# 021_BUTTONs_LEDs.net
KiCad netlist of a schematic drawn in Altium Designer
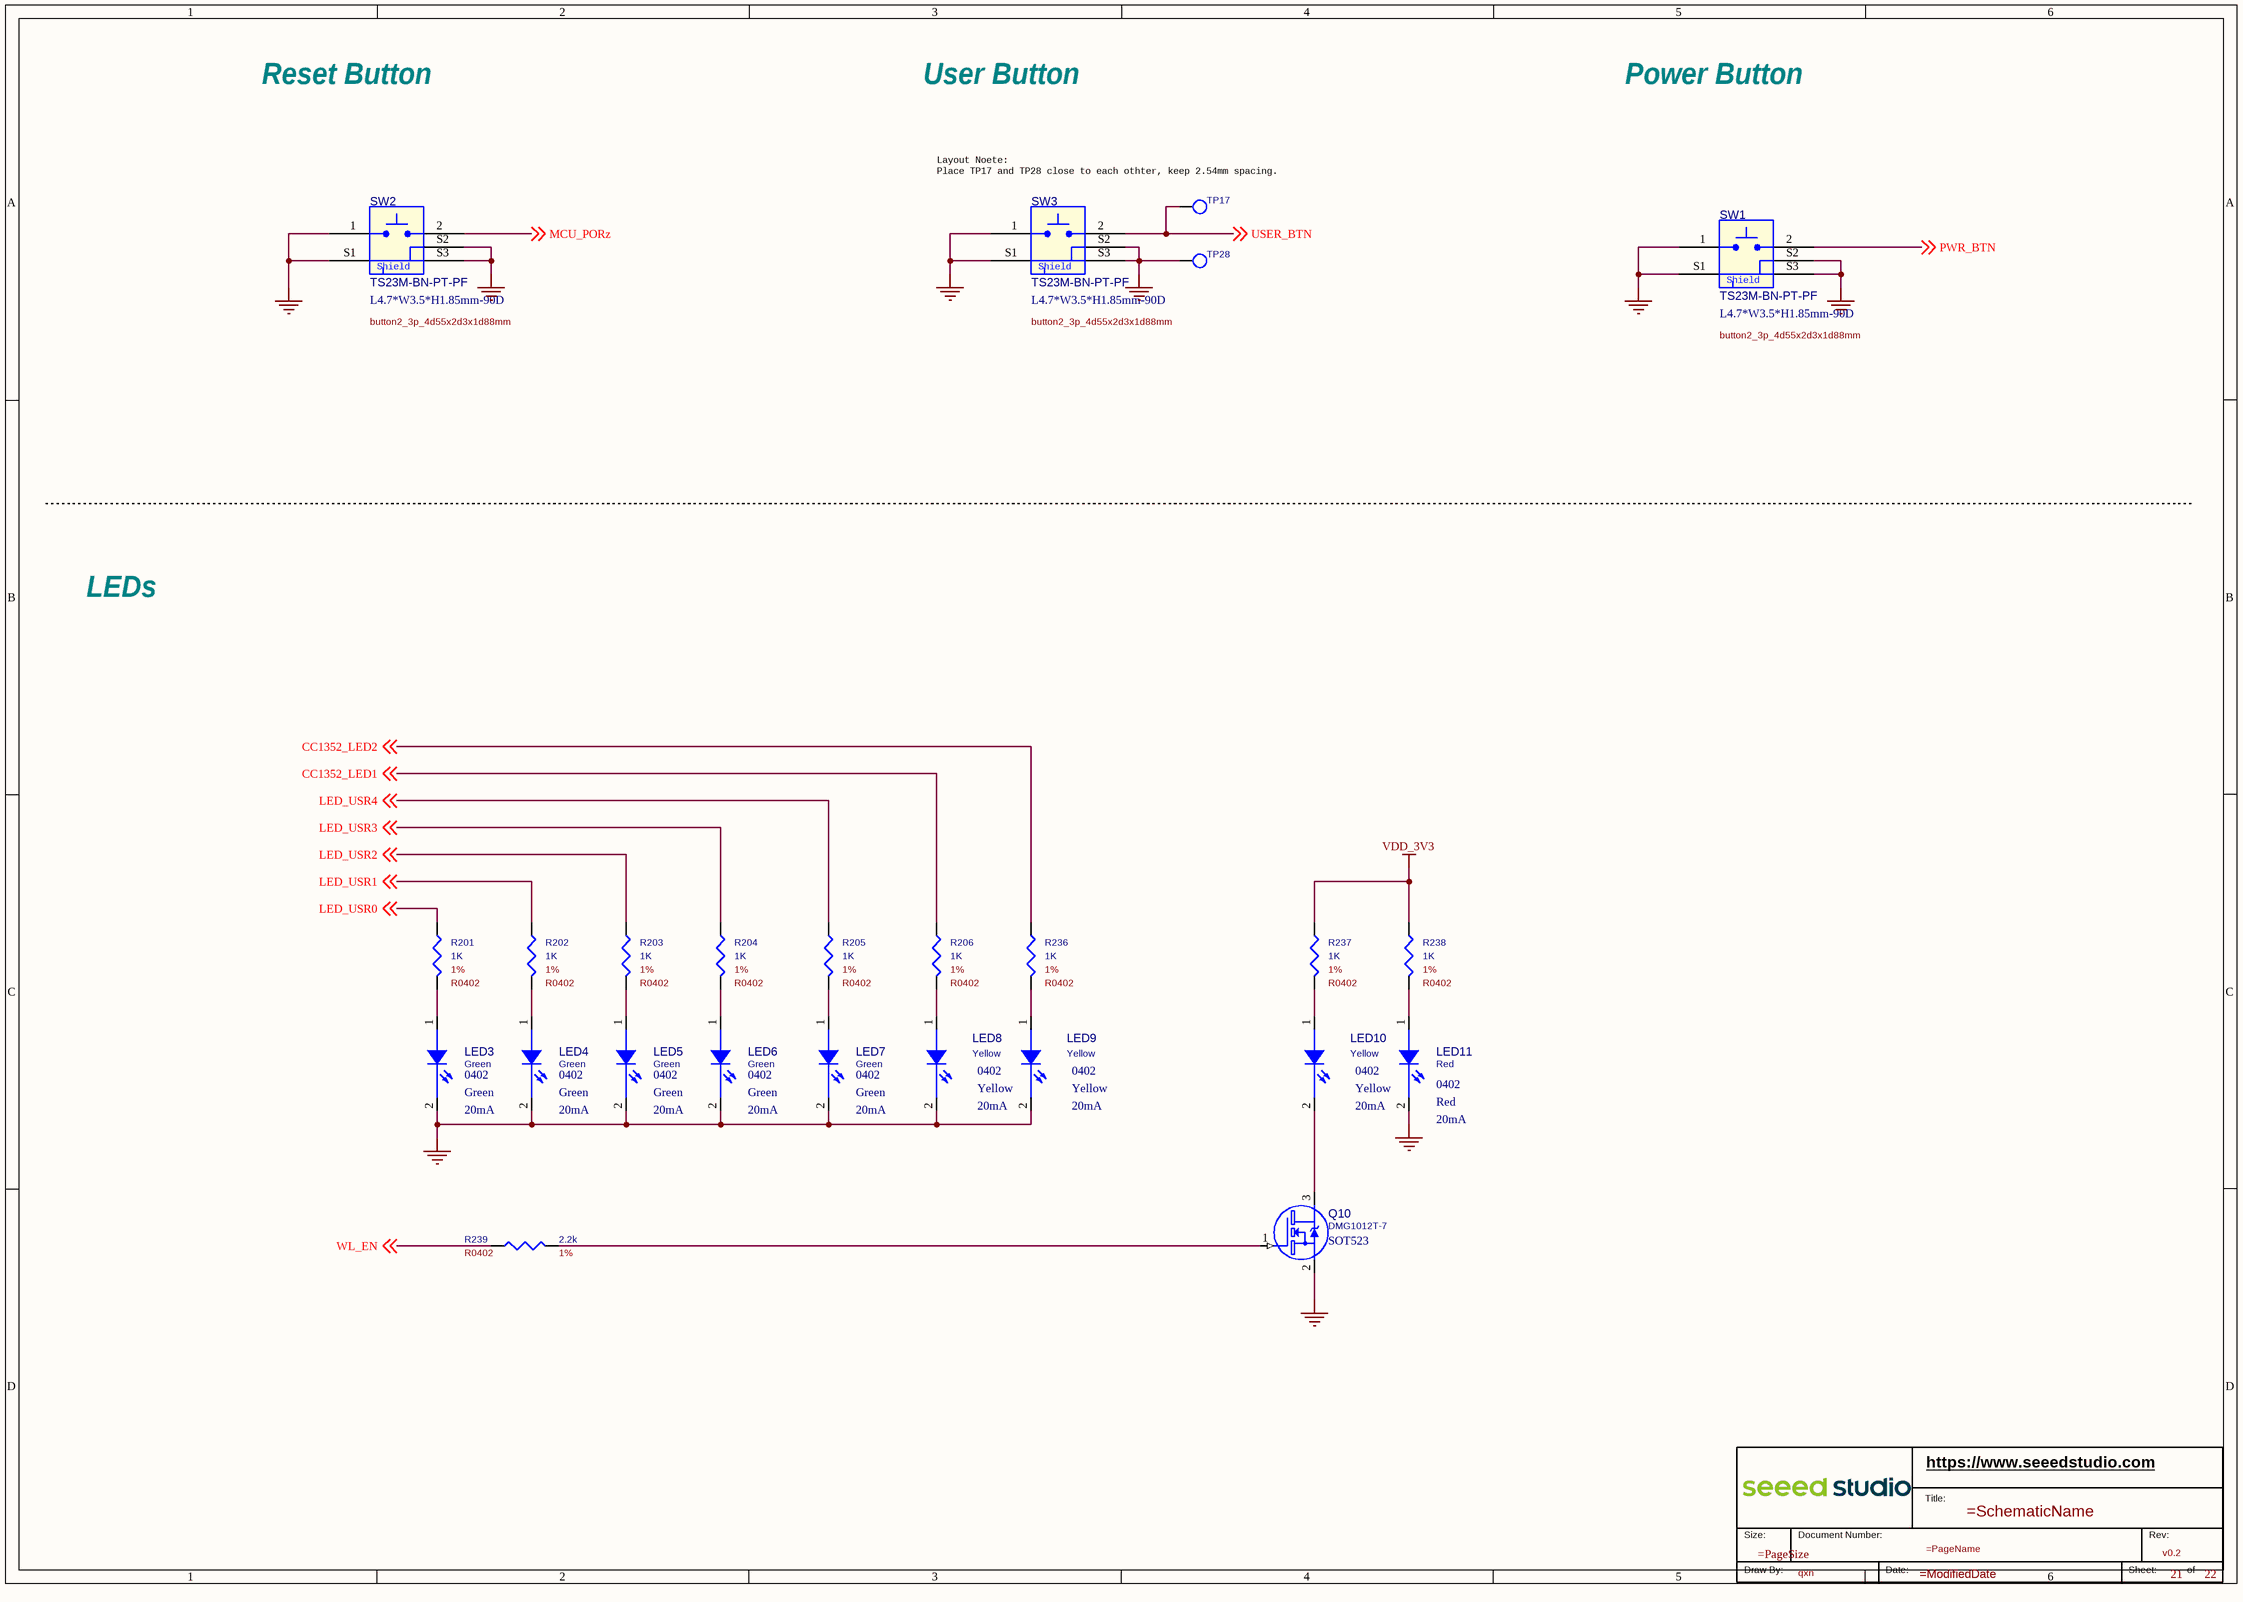
[diagram p0: 021_BUTTONs & LEDs.SchDoc]

(export (version "E")
  (design (tool "Eeschema 10.0.6"))
  (components
    (comp (ref "LED3")
      (value "Green")
      (footprint "led0402")
      (description "DIO, LED, Green, 20mA, --, --, 0402")
      (fields
        (field (name "MANUFACTURER") "Bright")
        (field (name "MANUFACTURER PART NUMBER") "19-217/BHC-ZL1M2RY/3T")
        (field (name "PACKAGE SIZE") "0402")
        (field (name "LED COLOR") "Green")
        (field (name "RATED CURRENT") "20mA")
      )
      (libsource (lib "*") (part "Single LED"))
    )
    (comp (ref "LED4")
      (value "Green")
      (footprint "led0402")
      (description "DIO, LED, Green, 20mA, --, --, 0402")
      (fields
        (field (name "MANUFACTURER") "Bright")
        (field (name "MANUFACTURER PART NUMBER") "19-217/BHC-ZL1M2RY/3T")
        (field (name "PACKAGE SIZE") "0402")
        (field (name "LED COLOR") "Green")
        (field (name "RATED CURRENT") "20mA")
      )
      (libsource (lib "*") (part "Single LED"))
    )
    (comp (ref "LED5")
      (value "Green")
      (footprint "led0402")
      (description "DIO, LED, Green, 20mA, --, --, 0402")
      (fields
        (field (name "MANUFACTURER") "Bright")
        (field (name "MANUFACTURER PART NUMBER") "19-217/BHC-ZL1M2RY/3T")
        (field (name "PACKAGE SIZE") "0402")
        (field (name "LED COLOR") "Green")
        (field (name "RATED CURRENT") "20mA")
      )
      (libsource (lib "*") (part "Single LED"))
    )
    (comp (ref "LED6")
      (value "Green")
      (footprint "led0402")
      (description "DIO, LED, Green, 20mA, --, --, 0402")
      (fields
        (field (name "MANUFACTURER") "Bright")
        (field (name "MANUFACTURER PART NUMBER") "19-217/BHC-ZL1M2RY/3T")
        (field (name "PACKAGE SIZE") "0402")
        (field (name "LED COLOR") "Green")
        (field (name "RATED CURRENT") "20mA")
      )
      (libsource (lib "*") (part "Single LED"))
    )
    (comp (ref "LED7")
      (value "Green")
      (footprint "led0402")
      (description "DIO, LED, Green, 20mA, --, --, 0402")
      (fields
        (field (name "MANUFACTURER") "Bright")
        (field (name "MANUFACTURER PART NUMBER") "19-217/BHC-ZL1M2RY/3T")
        (field (name "PACKAGE SIZE") "0402")
        (field (name "LED COLOR") "Green")
        (field (name "RATED CURRENT") "20mA")
      )
      (libsource (lib "*") (part "Single LED"))
    )
    (comp (ref "LED8")
      (value "Yellow")
      (footprint "led0402")
      (description "DIO, LED, Yellow, 20mA, --, --, 0402")
      (fields
        (field (name "PACKAGE SIZE") "0402")
        (field (name "LED COLOR") "Yellow")
        (field (name "RATED CURRENT") "20mA")
        (field (name "MANUFACTURER") "Everlight")
        (field (name "Comment") "Single LED")
      )
      (libsource (lib "*") (part "Single LED"))
    )
    (comp (ref "LED9")
      (value "Yellow")
      (footprint "led0402")
      (description "DIO, LED, Yellow, 20mA, --, --, 0402")
      (fields
        (field (name "PACKAGE SIZE") "0402")
        (field (name "LED COLOR") "Yellow")
        (field (name "RATED CURRENT") "20mA")
        (field (name "MANUFACTURER") "Everlight")
        (field (name "Comment") "Single LED")
      )
      (libsource (lib "*") (part "Single LED"))
    )
    (comp (ref "LED10")
      (value "Yellow")
      (footprint "led0402")
      (description "DIO, LED, Yellow, 20mA, --, --, 0402")
      (fields
        (field (name "PACKAGE SIZE") "0402")
        (field (name "LED COLOR") "Yellow")
        (field (name "RATED CURRENT") "20mA")
        (field (name "MANUFACTURER") "Everlight")
        (field (name "Comment") "Single LED")
      )
      (libsource (lib "*") (part "Single LED"))
    )
    (comp (ref "LED11")
      (value "Red")
      (footprint "led0402")
      (description "DIO, LED, Red, 20mA, , , 0402")
      (fields
        (field (name "MANUFACTURER") "Bright")
        (field (name "MANUFACTURER PART NUMBER") "19-217/BHC-ZL1M2RY/3T")
        (field (name "PACKAGE SIZE") "0402")
        (field (name "LED COLOR") "Red")
        (field (name "RATED CURRENT") "20mA")
      )
      (libsource (lib "*") (part "Single LED"))
    )
    (comp (ref "Q10")
      (value "DMG1012T-7")
      (footprint "SOT_523")
      (description "XSTR, MOSFET, N-Channel, DMG1012T-7, 20V, 630mA, SOT523, SMD")
      (fields
        (field (name "MANUFACTURER") "Diodes")
        (field (name "PACKAGE SIZE") "SOT523")
        (field (name "Comment") "NMOS_123")
      )
      (libsource (lib "*") (part "NMOS_123"))
    )
    (comp (ref "R201")
      (value "1K")
      (footprint "R0402")
      (description "RES, Thick Film, 1K, 1%, 1/16W, SMD, 0402")
      (fields
        (field (name "RATING") "1%")
        (field (name "PCB FOOTPRINT") "R0402")
        (field (name "MANUFACTURER PART NUMBER") "RC0402JR-071KL")
        (field (name "MANUFACTURER") "YAGEO")
      )
      (libsource (lib "*") (part "R"))
    )
    (comp (ref "R202")
      (value "1K")
      (footprint "R0402")
      (description "RES, Thick Film, 1K, 1%, 1/16W, SMD, 0402")
      (fields
        (field (name "RATING") "1%")
        (field (name "PCB FOOTPRINT") "R0402")
        (field (name "MANUFACTURER PART NUMBER") "RC0402JR-071KL")
        (field (name "MANUFACTURER") "YAGEO")
      )
      (libsource (lib "*") (part "R"))
    )
    (comp (ref "R203")
      (value "1K")
      (footprint "R0402")
      (description "RES, Thick Film, 1K, 1%, 1/16W, SMD, 0402")
      (fields
        (field (name "RATING") "1%")
        (field (name "PCB FOOTPRINT") "R0402")
        (field (name "MANUFACTURER PART NUMBER") "RC0402JR-071KL")
        (field (name "MANUFACTURER") "YAGEO")
      )
      (libsource (lib "*") (part "R"))
    )
    (comp (ref "R204")
      (value "1K")
      (footprint "R0402")
      (description "RES, Thick Film, 1K, 1%, 1/16W, SMD, 0402")
      (fields
        (field (name "RATING") "1%")
        (field (name "PCB FOOTPRINT") "R0402")
        (field (name "MANUFACTURER PART NUMBER") "RC0402JR-071KL")
        (field (name "MANUFACTURER") "YAGEO")
      )
      (libsource (lib "*") (part "R"))
    )
    (comp (ref "R205")
      (value "1K")
      (footprint "R0402")
      (description "RES, Thick Film, 1K, 1%, 1/16W, SMD, 0402")
      (fields
        (field (name "RATING") "1%")
        (field (name "PCB FOOTPRINT") "R0402")
        (field (name "MANUFACTURER PART NUMBER") "RC0402JR-071KL")
        (field (name "MANUFACTURER") "YAGEO")
      )
      (libsource (lib "*") (part "R"))
    )
    (comp (ref "R206")
      (value "1K")
      (footprint "R0402")
      (description "RES, Thick Film, 1K, 1%, 1/16W, SMD, 0402")
      (fields
        (field (name "RATING") "1%")
        (field (name "PCB FOOTPRINT") "R0402")
        (field (name "MANUFACTURER PART NUMBER") "RC0402JR-071KL")
        (field (name "MANUFACTURER") "YAGEO")
      )
      (libsource (lib "*") (part "R"))
    )
    (comp (ref "R236")
      (value "1K")
      (footprint "R0402")
      (description "RES, Thick Film, 1K, 1%, 1/16W, SMD, 0402")
      (fields
        (field (name "RATING") "1%")
        (field (name "PCB FOOTPRINT") "R0402")
        (field (name "MANUFACTURER PART NUMBER") "RC0402JR-071KL")
        (field (name "MANUFACTURER") "YAGEO")
      )
      (libsource (lib "*") (part "R"))
    )
    (comp (ref "R237")
      (value "1K")
      (footprint "R0402")
      (description "RES, Thick Film, 1K, 1%, 1/16W, SMD, 0402")
      (fields
        (field (name "RATING") "1%")
        (field (name "PCB FOOTPRINT") "R0402")
        (field (name "MANUFACTURER") "YAGEO")
        (field (name "MANUFACTURER PART NUMBER") "RC0402JR-071KL")
      )
      (libsource (lib "*") (part "R"))
    )
    (comp (ref "R238")
      (value "1K")
      (footprint "R0402")
      (description "RES, Thick Film, 1K, 1%, 1/16W, SMD, 0402")
      (fields
        (field (name "RATING") "1%")
        (field (name "PCB FOOTPRINT") "R0402")
        (field (name "MANUFACTURER PART NUMBER") "RC0402JR-071KL")
        (field (name "MANUFACTURER") "YAGEO")
      )
      (libsource (lib "*") (part "R"))
    )
    (comp (ref "R239")
      (value "2.2k")
      (footprint "R0402")
      (description "RES, Thick Film, 2.2k, 1%, 1/16W, SMD, 0402")
      (fields
        (field (name "RATING") "1%")
        (field (name "PCB FOOTPRINT") "R0402")
        (field (name "MANUFACTURER") "YAGEO")
        (field (name "Comment") "R")
      )
      (libsource (lib "") (part "R_1"))
    )
    (comp (ref "SW1")
      (value "TS23M-BN-PT-PF")
      (footprint "button2_3p_4d55x2d3x1d88mm")
      (description "SW, Tactile Switch, TS23M-BN-PT-PF, --, 5, SMD")
      (fields
        (field (name "PCB FOOTPRINT") "button2_3p_4d55x2d3x1d88mm")
        (field (name "MANUFACTURER") "ROKI")
        (field (name "PACKAGE SIZE") "L4.7*W3.5*H1.85mm-90D")
        (field (name "Comment") "Tactile Switch_2+3P")
      )
      (libsource (lib "*") (part "Tactile Switch_2+3P"))
    )
    (comp (ref "SW2")
      (value "TS23M-BN-PT-PF")
      (footprint "button2_3p_4d55x2d3x1d88mm")
      (description "SW, Tactile Switch, TS23M-BN-PT-PF, --, 5, SMD")
      (fields
        (field (name "PCB FOOTPRINT") "button2_3p_4d55x2d3x1d88mm")
        (field (name "PACKAGE SIZE") "L4.7*W3.5*H1.85mm-90D")
        (field (name "MANUFACTURER") "ROKI")
        (field (name "Comment") "Tactile Switch_2+3P")
      )
      (libsource (lib "*") (part "Tactile Switch_2+3P"))
    )
    (comp (ref "SW3")
      (value "TS23M-BN-PT-PF")
      (footprint "button2_3p_4d55x2d3x1d88mm")
      (description "SW, Tactile Switch, TS23M-BN-PT-PF, --, 5, SMD")
      (fields
        (field (name "PCB FOOTPRINT") "button2_3p_4d55x2d3x1d88mm")
        (field (name "PACKAGE SIZE") "L4.7*W3.5*H1.85mm-90D")
        (field (name "MANUFACTURER") "ROKI")
        (field (name "Comment") "Tactile Switch_2+3P")
      )
      (libsource (lib "*") (part "Tactile Switch_2+3P"))
    )
    (comp (ref "TP17")
      (value "Test Point")
      (footprint "tp1-8040")
      (description "MISC, Test Point, Test Point, SMD, TP35S_SMD")
      (libsource (lib "*") (part "Test Point"))
    )
    (comp (ref "TP28")
      (value "Test Point")
      (footprint "tp1-8040")
      (description "MISC, Test Point, Test Point, SMD, TP35S_SMD")
      (libsource (lib "*") (part "Test Point"))
    )
  )
  (nets
    (net (code "1") (name "CC1352_LED1") (class "Default")
      (node (ref "R206") (pin "1") (pinfunction "1_1") (pintype "passive"))
    )
    (net (code "2") (name "CC1352_LED2") (class "Default")
      (node (ref "R236") (pin "1") (pinfunction "1_1") (pintype "passive"))
    )
    (net (code "3") (name "GND") (class "Default")
      (node (ref "LED11") (pin "2") (pinfunction "C_2") (pintype "passive"))
      (node (ref "LED3") (pin "2") (pinfunction "C_2") (pintype "passive"))
      (node (ref "LED4") (pin "2") (pinfunction "C_2") (pintype "passive"))
      (node (ref "LED5") (pin "2") (pinfunction "C_2") (pintype "passive"))
      (node (ref "LED6") (pin "2") (pinfunction "C_2") (pintype "passive"))
      (node (ref "LED7") (pin "2") (pinfunction "C_2") (pintype "passive"))
      (node (ref "LED8") (pin "2") (pinfunction "C_2") (pintype "passive"))
      (node (ref "LED9") (pin "2") (pinfunction "C_2") (pintype "passive"))
      (node (ref "Q10") (pin "2") (pinfunction "S_2") (pintype "passive"))
      (node (ref "SW1") (pin "1") (pinfunction "A2_1") (pintype "passive"))
      (node (ref "SW1") (pin "S1") (pinfunction "A1_S1") (pintype "passive"))
      (node (ref "SW1") (pin "S2") (pinfunction "B2_S2") (pintype "passive"))
      (node (ref "SW1") (pin "S3") (pinfunction "B1_S3") (pintype "passive"))
      (node (ref "SW2") (pin "1") (pinfunction "A2_1") (pintype "passive"))
      (node (ref "SW2") (pin "S1") (pinfunction "A1_S1") (pintype "passive"))
      (node (ref "SW2") (pin "S2") (pinfunction "B2_S2") (pintype "passive"))
      (node (ref "SW2") (pin "S3") (pinfunction "B1_S3") (pintype "passive"))
      (node (ref "SW3") (pin "1") (pinfunction "A2_1") (pintype "passive"))
      (node (ref "SW3") (pin "S1") (pinfunction "A1_S1") (pintype "passive"))
      (node (ref "SW3") (pin "S2") (pinfunction "B2_S2") (pintype "passive"))
      (node (ref "SW3") (pin "S3") (pinfunction "B1_S3") (pintype "passive"))
      (node (ref "TP28") (pin "1") (pinfunction "TP_1") (pintype "passive"))
    )
    (net (code "4") (name "LED_USR0") (class "Default")
      (node (ref "R201") (pin "1") (pinfunction "1_1") (pintype "passive"))
    )
    (net (code "5") (name "LED_USR1") (class "Default")
      (node (ref "R202") (pin "1") (pinfunction "1_1") (pintype "passive"))
    )
    (net (code "6") (name "LED_USR2") (class "Default")
      (node (ref "R203") (pin "1") (pinfunction "1_1") (pintype "passive"))
    )
    (net (code "7") (name "LED_USR3") (class "Default")
      (node (ref "R204") (pin "1") (pinfunction "1_1") (pintype "passive"))
    )
    (net (code "8") (name "LED_USR4") (class "Default")
      (node (ref "R205") (pin "1") (pinfunction "1_1") (pintype "passive"))
    )
    (net (code "9") (name "MCU_PORz") (class "Default")
      (node (ref "SW2") (pin "2") (pinfunction "B3_2") (pintype "passive"))
    )
    (net (code "10") (name "Net-(LED3-A)") (class "Default")
      (node (ref "LED3") (pin "1") (pinfunction "A_1") (pintype "passive"))
      (node (ref "R201") (pin "2") (pinfunction "2_2") (pintype "passive"))
    )
    (net (code "11") (name "Net-(LED4-A)") (class "Default")
      (node (ref "LED4") (pin "1") (pinfunction "A_1") (pintype "passive"))
      (node (ref "R202") (pin "2") (pinfunction "2_2") (pintype "passive"))
    )
    (net (code "12") (name "Net-(LED5-A)") (class "Default")
      (node (ref "LED5") (pin "1") (pinfunction "A_1") (pintype "passive"))
      (node (ref "R203") (pin "2") (pinfunction "2_2") (pintype "passive"))
    )
    (net (code "13") (name "Net-(LED6-A)") (class "Default")
      (node (ref "LED6") (pin "1") (pinfunction "A_1") (pintype "passive"))
      (node (ref "R204") (pin "2") (pinfunction "2_2") (pintype "passive"))
    )
    (net (code "14") (name "Net-(LED7-A)") (class "Default")
      (node (ref "LED7") (pin "1") (pinfunction "A_1") (pintype "passive"))
      (node (ref "R205") (pin "2") (pinfunction "2_2") (pintype "passive"))
    )
    (net (code "15") (name "Net-(LED8-A)") (class "Default")
      (node (ref "LED8") (pin "1") (pinfunction "A_1") (pintype "passive"))
      (node (ref "R206") (pin "2") (pinfunction "2_2") (pintype "passive"))
    )
    (net (code "16") (name "Net-(LED9-A)") (class "Default")
      (node (ref "LED9") (pin "1") (pinfunction "A_1") (pintype "passive"))
      (node (ref "R236") (pin "2") (pinfunction "2_2") (pintype "passive"))
    )
    (net (code "17") (name "Net-(LED10-A)") (class "Default")
      (node (ref "LED10") (pin "1") (pinfunction "A_1") (pintype "passive"))
      (node (ref "R237") (pin "2") (pinfunction "2_2") (pintype "passive"))
    )
    (net (code "18") (name "Net-(LED10-C)") (class "Default")
      (node (ref "LED10") (pin "2") (pinfunction "C_2") (pintype "passive"))
      (node (ref "Q10") (pin "3") (pinfunction "D_3") (pintype "passive"))
    )
    (net (code "19") (name "Net-(LED11-A)") (class "Default")
      (node (ref "LED11") (pin "1") (pinfunction "A_1") (pintype "passive"))
      (node (ref "R238") (pin "2") (pinfunction "2_2") (pintype "passive"))
    )
    (net (code "20") (name "Net-(Q10-G)") (class "Default")
      (node (ref "Q10") (pin "1") (pinfunction "G_1") (pintype "input"))
      (node (ref "R239") (pin "2") (pinfunction "2_2") (pintype "passive"))
    )
    (net (code "21") (name "PWR_BTN") (class "Default")
      (node (ref "SW1") (pin "2") (pinfunction "B3_2") (pintype "passive"))
    )
    (net (code "22") (name "USER_BTN") (class "Default")
      (node (ref "SW3") (pin "2") (pinfunction "B3_2") (pintype "passive"))
      (node (ref "TP17") (pin "1") (pinfunction "TP_1") (pintype "passive"))
    )
    (net (code "23") (name "VDD_3V3") (class "Default")
      (node (ref "R237") (pin "1") (pinfunction "1_1") (pintype "passive"))
      (node (ref "R238") (pin "1") (pinfunction "1_1") (pintype "passive"))
    )
    (net (code "24") (name "WL_EN") (class "Default")
      (node (ref "R239") (pin "1") (pinfunction "1_1") (pintype "passive"))
    )
  )
)
